# 09_FPGA_HSIO_B4.net
KiCad netlist of a schematic drawn in Altium Designer
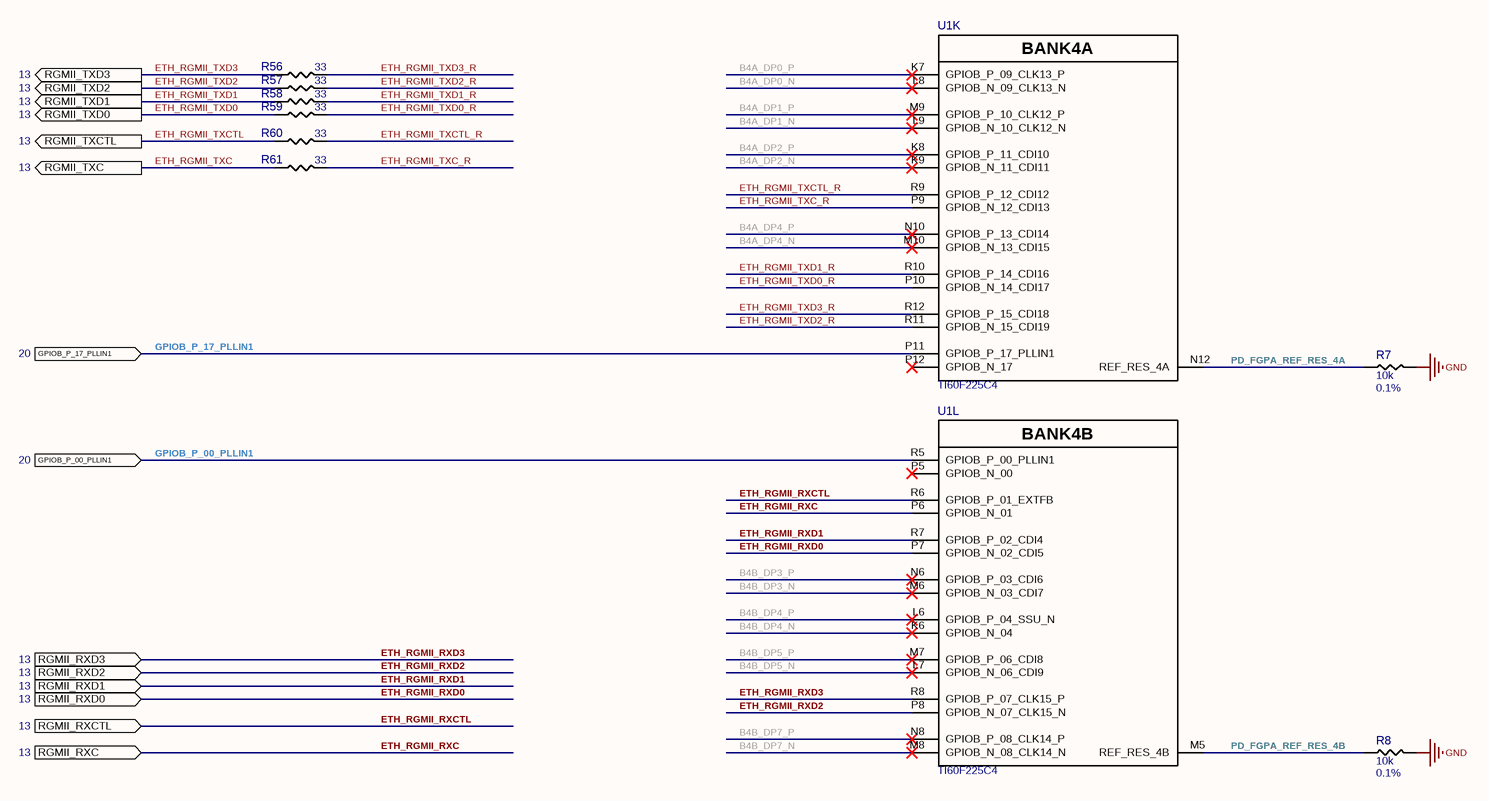
[diagram p0: 09_FPGA_HSIO_B4.SchDoc]

(export (version "E")
  (design (tool "Eeschema 10.0.6"))
  (components
    (comp (ref "R7")
      (value "10k")
      (footprint "RESC1005X03N")
      (description "RES SMD 10K OHM 0.1% 1/16W 0402")
      (fields (field (name "PART NUMBER") "RT0402BRD0710KL") (field (name "TOL") "0.1%"))
      (libsource (lib "Database") (part "Resistor_ENG"))
    )
    (comp (ref "R8")
      (value "10k")
      (footprint "RESC1005X03N")
      (description "RES SMD 10K OHM 0.1% 1/16W 0402")
      (fields (field (name "PART NUMBER") "RT0402BRD0710KL") (field (name "TOL") "0.1%"))
      (libsource (lib "Database") (part "Resistor_ENG"))
    )
    (comp (ref "R56")
      (value "33")
      (footprint "RESC1005X03N")
      (description "RES SMD 33 OHM 1% 1/16W 0402")
      (fields (field (name "PART NUMBER") "RC0402FR-0733RL"))
      (libsource (lib "Database") (part "Resistor_ENG"))
    )
    (comp (ref "R57")
      (value "33")
      (footprint "RESC1005X03N")
      (description "RES SMD 33 OHM 1% 1/16W 0402")
      (fields (field (name "PART NUMBER") "RC0402FR-0733RL"))
      (libsource (lib "Database") (part "Resistor_ENG"))
    )
    (comp (ref "R58")
      (value "33")
      (footprint "RESC1005X03N")
      (description "RES SMD 33 OHM 1% 1/16W 0402")
      (fields (field (name "PART NUMBER") "RC0402FR-0733RL"))
      (libsource (lib "Database") (part "Resistor_ENG"))
    )
    (comp (ref "R59")
      (value "33")
      (footprint "RESC1005X03N")
      (description "RES SMD 33 OHM 1% 1/16W 0402")
      (fields (field (name "PART NUMBER") "RC0402FR-0733RL"))
      (libsource (lib "Database") (part "Resistor_ENG"))
    )
    (comp (ref "R60")
      (value "33")
      (footprint "RESC1005X03N")
      (description "RES SMD 33 OHM 1% 1/16W 0402")
      (fields (field (name "PART NUMBER") "RC0402FR-0733RL"))
      (libsource (lib "Database") (part "Resistor_ENG"))
    )
    (comp (ref "R61")
      (value "33")
      (footprint "RESC1005X03N")
      (description "RES SMD 33 OHM 1% 1/16W 0402")
      (fields (field (name "PART NUMBER") "RC0402FR-0733RL"))
      (libsource (lib "Database") (part "Resistor_ENG"))
    )
    (comp (ref "U1")
      (value "TI60F225C4")
      (footprint "BGA225C65P15X15_1000X1000X100")
      (description "FPGA TITAN 140HSIO 4PLL 225BGA")
      (libsource (lib "Database") (part "TI60F225"))
    )
  )
  (nets
    (net (code "1") (name "/B4A_DP0_N") (class "Default")
      (node (ref "U1") (pin "L8") (pinfunction "GPIOB_N_09_CLK13_N_L8") (pintype "passive+no_connect"))
    )
    (net (code "2") (name "/B4A_DP0_P") (class "Default")
      (node (ref "U1") (pin "K7") (pinfunction "GPIOB_P_09_CLK13_P_K7") (pintype "passive+no_connect"))
    )
    (net (code "3") (name "/B4A_DP1_N") (class "Default")
      (node (ref "U1") (pin "L9") (pinfunction "GPIOB_N_10_CLK12_N_L9") (pintype "passive+no_connect"))
    )
    (net (code "4") (name "/B4A_DP1_P") (class "Default")
      (node (ref "U1") (pin "M9") (pinfunction "GPIOB_P_10_CLK12_P_M9") (pintype "passive+no_connect"))
    )
    (net (code "5") (name "/B4A_DP2_N") (class "Default")
      (node (ref "U1") (pin "K9") (pinfunction "GPIOB_N_11_CDI11_K9") (pintype "passive+no_connect"))
    )
    (net (code "6") (name "/B4A_DP2_P") (class "Default")
      (node (ref "U1") (pin "K8") (pinfunction "GPIOB_P_11_CDI10_K8") (pintype "passive+no_connect"))
    )
    (net (code "7") (name "/B4A_DP4_N") (class "Default")
      (node (ref "U1") (pin "M10") (pinfunction "GPIOB_N_13_CDI15_M10") (pintype "passive+no_connect"))
    )
    (net (code "8") (name "/B4A_DP4_P") (class "Default")
      (node (ref "U1") (pin "N10") (pinfunction "GPIOB_P_13_CDI14_N10") (pintype "passive+no_connect"))
    )
    (net (code "9") (name "/B4B_DP3_N") (class "Default")
      (node (ref "U1") (pin "M6") (pinfunction "GPIOB_N_03_CDI7_M6") (pintype "passive+no_connect"))
    )
    (net (code "10") (name "/B4B_DP3_P") (class "Default")
      (node (ref "U1") (pin "N6") (pinfunction "GPIOB_P_03_CDI6_N6") (pintype "passive+no_connect"))
    )
    (net (code "11") (name "/B4B_DP4_N") (class "Default")
      (node (ref "U1") (pin "K6") (pinfunction "GPIOB_N_04_K6") (pintype "passive+no_connect"))
    )
    (net (code "12") (name "/B4B_DP4_P") (class "Default")
      (node (ref "U1") (pin "L6") (pinfunction "GPIOB_P_04_SSU_N_L6") (pintype "passive+no_connect"))
    )
    (net (code "13") (name "/B4B_DP5_N") (class "Default")
      (node (ref "U1") (pin "L7") (pinfunction "GPIOB_N_06_CDI9_L7") (pintype "passive+no_connect"))
    )
    (net (code "14") (name "/B4B_DP5_P") (class "Default")
      (node (ref "U1") (pin "M7") (pinfunction "GPIOB_P_06_CDI8_M7") (pintype "passive+no_connect"))
    )
    (net (code "15") (name "/B4B_DP7_N") (class "Default")
      (node (ref "U1") (pin "M8") (pinfunction "GPIOB_N_08_CLK14_N_M8") (pintype "passive+no_connect"))
    )
    (net (code "16") (name "/B4B_DP7_P") (class "Default")
      (node (ref "U1") (pin "N8") (pinfunction "GPIOB_P_08_CLK14_P_N8") (pintype "passive+no_connect"))
    )
    (net (code "17") (name "/ETH_RGMII_RXC") (class "Default")
      (node (ref "U1") (pin "P6") (pinfunction "GPIOB_N_01_P6") (pintype "passive"))
    )
    (net (code "18") (name "/ETH_RGMII_RXCTL") (class "Default")
      (node (ref "U1") (pin "R6") (pinfunction "GPIOB_P_01_EXTFB_R6") (pintype "passive"))
    )
    (net (code "19") (name "/ETH_RGMII_RXD0") (class "Default")
      (node (ref "U1") (pin "P7") (pinfunction "GPIOB_N_02_CDI5_P7") (pintype "passive"))
    )
    (net (code "20") (name "/ETH_RGMII_RXD1") (class "Default")
      (node (ref "U1") (pin "R7") (pinfunction "GPIOB_P_02_CDI4_R7") (pintype "passive"))
    )
    (net (code "21") (name "/ETH_RGMII_RXD2") (class "Default")
      (node (ref "U1") (pin "P8") (pinfunction "GPIOB_N_07_CLK15_N_P8") (pintype "passive"))
    )
    (net (code "22") (name "/ETH_RGMII_RXD3") (class "Default")
      (node (ref "U1") (pin "R8") (pinfunction "GPIOB_P_07_CLK15_P_R8") (pintype "passive"))
    )
    (net (code "23") (name "/ETH_RGMII_TXC") (class "Default")
      (node (ref "R61") (pin "1") (pinfunction "1_1") (pintype "passive"))
    )
    (net (code "24") (name "/ETH_RGMII_TXCTL") (class "Default")
      (node (ref "R60") (pin "1") (pinfunction "1_1") (pintype "passive"))
    )
    (net (code "25") (name "/ETH_RGMII_TXCTL_R") (class "Default")
      (node (ref "R60") (pin "2") (pinfunction "2_2") (pintype "passive"))
      (node (ref "U1") (pin "R9") (pinfunction "GPIOB_P_12_CDI12_R9") (pintype "passive"))
    )
    (net (code "26") (name "/ETH_RGMII_TXC_R") (class "Default")
      (node (ref "R61") (pin "2") (pinfunction "2_2") (pintype "passive"))
      (node (ref "U1") (pin "P9") (pinfunction "GPIOB_N_12_CDI13_P9") (pintype "passive"))
    )
    (net (code "27") (name "/ETH_RGMII_TXD0") (class "Default")
      (node (ref "R59") (pin "1") (pinfunction "1_1") (pintype "passive"))
    )
    (net (code "28") (name "/ETH_RGMII_TXD0_R") (class "Default")
      (node (ref "R59") (pin "2") (pinfunction "2_2") (pintype "passive"))
      (node (ref "U1") (pin "P10") (pinfunction "GPIOB_N_14_CDI17_P10") (pintype "passive"))
    )
    (net (code "29") (name "/ETH_RGMII_TXD1") (class "Default")
      (node (ref "R58") (pin "1") (pinfunction "1_1") (pintype "passive"))
    )
    (net (code "30") (name "/ETH_RGMII_TXD1_R") (class "Default")
      (node (ref "R58") (pin "2") (pinfunction "2_2") (pintype "passive"))
      (node (ref "U1") (pin "R10") (pinfunction "GPIOB_P_14_CDI16_R10") (pintype "passive"))
    )
    (net (code "31") (name "/ETH_RGMII_TXD2") (class "Default")
      (node (ref "R57") (pin "1") (pinfunction "1_1") (pintype "passive"))
    )
    (net (code "32") (name "/ETH_RGMII_TXD2_R") (class "Default")
      (node (ref "R57") (pin "2") (pinfunction "2_2") (pintype "passive"))
      (node (ref "U1") (pin "R11") (pinfunction "GPIOB_N_15_CDI19_R11") (pintype "passive"))
    )
    (net (code "33") (name "/ETH_RGMII_TXD3") (class "Default")
      (node (ref "R56") (pin "1") (pinfunction "1_1") (pintype "passive"))
    )
    (net (code "34") (name "/ETH_RGMII_TXD3_R") (class "Default")
      (node (ref "R56") (pin "2") (pinfunction "2_2") (pintype "passive"))
      (node (ref "U1") (pin "R12") (pinfunction "GPIOB_P_15_CDI18_R12") (pintype "passive"))
    )
    (net (code "35") (name "/GPIOB_P_00_PLLIN1") (class "Default")
      (node (ref "U1") (pin "R5") (pinfunction "GPIOB_P_00_PLLIN1_R5") (pintype "passive"))
    )
    (net (code "36") (name "/GPIOB_P_17_PLLIN1") (class "Default")
      (node (ref "U1") (pin "P11") (pinfunction "GPIOB_P_17_PLLIN1_P11") (pintype "passive"))
    )
    (net (code "37") (name "/PD_FGPA_REF_RES_4A") (class "Default")
      (node (ref "R7") (pin "1") (pinfunction "1_1") (pintype "passive"))
      (node (ref "U1") (pin "N12") (pinfunction "REF_RES_4A_N12") (pintype "passive"))
    )
    (net (code "38") (name "/PD_FGPA_REF_RES_4B") (class "Default")
      (node (ref "R8") (pin "1") (pinfunction "1_1") (pintype "passive"))
      (node (ref "U1") (pin "M5") (pinfunction "REF_RES_4B_M5") (pintype "passive"))
    )
    (net (code "39") (name "GND") (class "Default")
      (node (ref "R7") (pin "2") (pinfunction "2_2") (pintype "passive"))
      (node (ref "R8") (pin "2") (pinfunction "2_2") (pintype "passive"))
    )
    (net (code "40") (name "unconnected-(U1K-GPIOB_N_17-PadP12)") (class "Default")
      (node (ref "U1") (pin "P12") (pinfunction "GPIOB_N_17_P12") (pintype "passive+no_connect"))
    )
    (net (code "41") (name "unconnected-(U1L-GPIOB_N_00-PadP5)") (class "Default")
      (node (ref "U1") (pin "P5") (pinfunction "GPIOB_N_00_P5") (pintype "passive+no_connect"))
    )
  )
)
